# llrf_afe_fpga_conf.net
KiCad netlist of a schematic drawn in Altium Designer
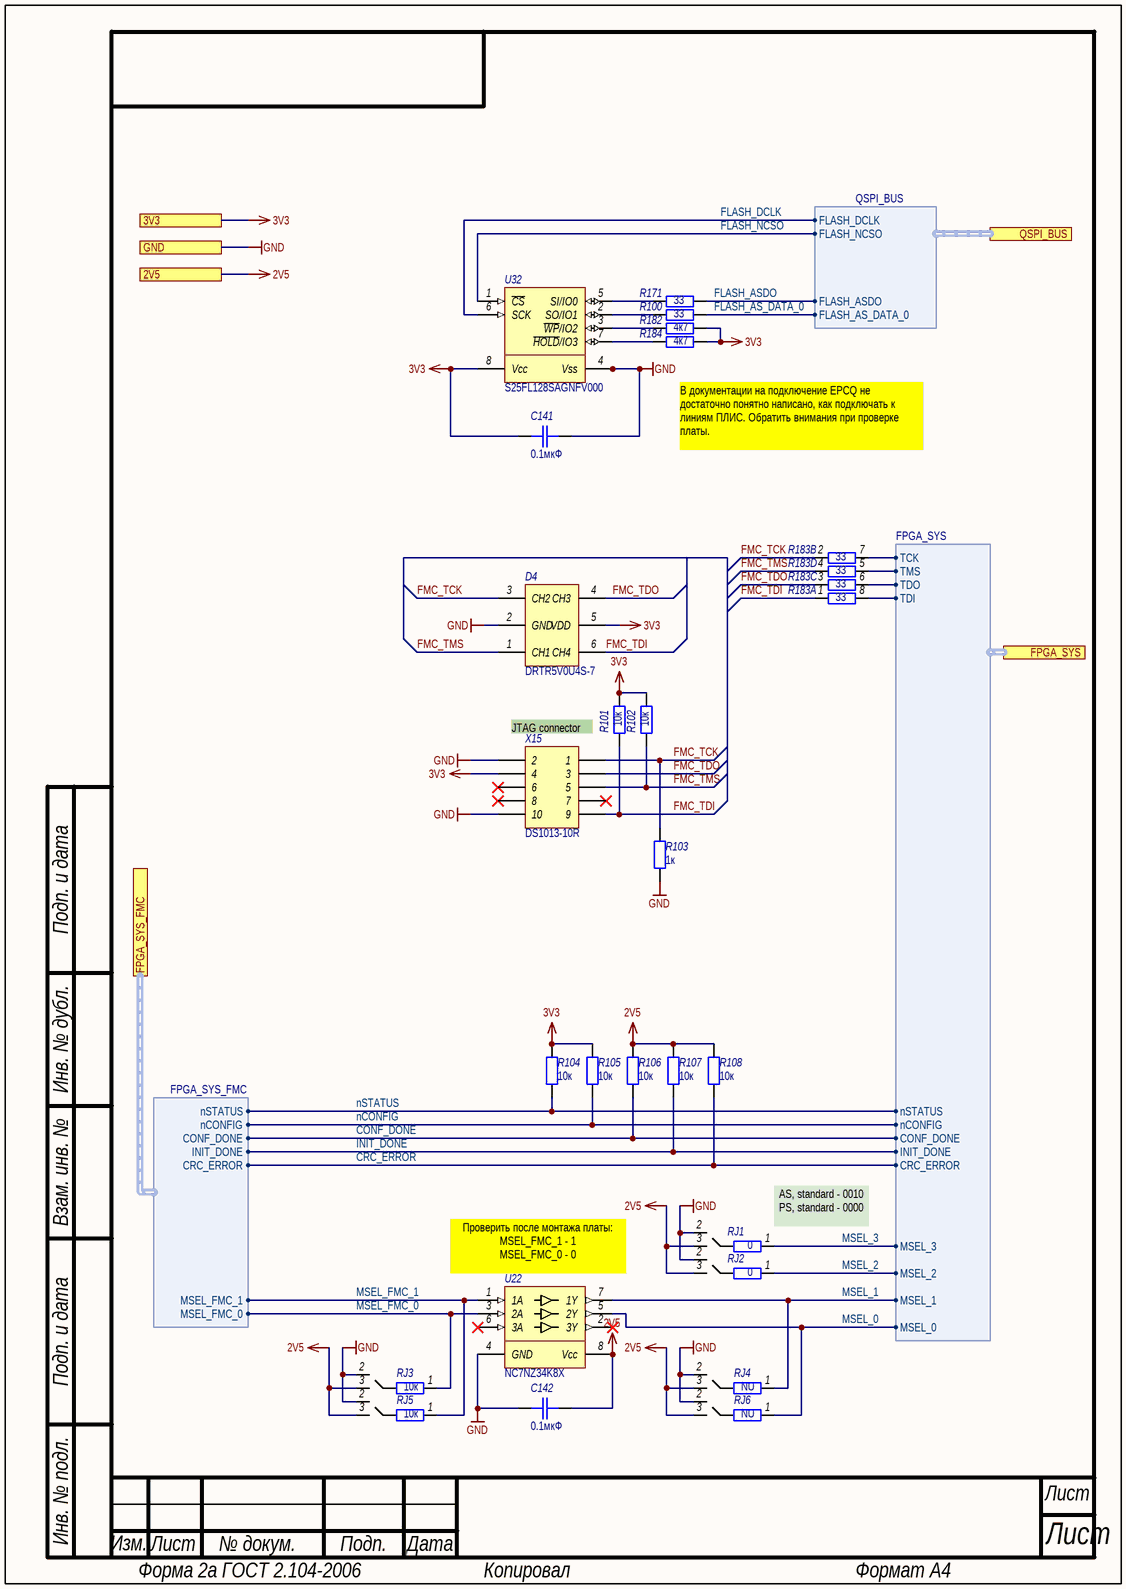
[diagram p0: llrf_afe_fpga_conf.SchDoc]

(export (version "E")
  (design (tool "Eeschema 10.0.6"))
  (components
    (comp (ref "C141")
      (value "0.1мкФ")
      (footprint "SMD_C0402")
      (description "Capacitor")
      (libsource (lib "Passive") (part "Capacitor"))
    )
    (comp (ref "C142")
      (value "0.1мкФ")
      (footprint "SMD_C0402")
      (description "Capacitor")
      (libsource (lib "Passive") (part "Capacitor"))
    )
    (comp (ref "D4")
      (value "DRTR5V0U4S")
      (footprint "SOT-363")
      (description "4 CHANNEL LOW CAPACITANCE TVS DIODE ARRAY")
      (fields (field (name "НАИМЕНОВАНИЕ") "DRTR5V0U4S-7"))
      (libsource (lib "Diod") (part "DRTR5V0U4S"))
    )
    (comp (ref "R100")
      (value "33")
      (footprint "SMD_0603")
      (description "PE1206DRM470R01L")
      (libsource (lib "Passive") (part "Resistor"))
    )
    (comp (ref "R101")
      (value "10к")
      (footprint "SMD_0603")
      (description "Resistor")
      (libsource (lib "") (part "Resistor_1"))
    )
    (comp (ref "R102")
      (value "10к")
      (footprint "SMD_0603")
      (description "Resistor")
      (libsource (lib "") (part "Resistor_1"))
    )
    (comp (ref "R103")
      (value "1к")
      (footprint "SMD_0603")
      (description "Resistor")
      (libsource (lib "") (part "Resistor_1"))
    )
    (comp (ref "R104")
      (value "10к")
      (footprint "SMD_0603")
      (description "Resistor")
      (libsource (lib "") (part "Resistor_1"))
    )
    (comp (ref "R105")
      (value "10к")
      (footprint "SMD_0603")
      (description "Resistor")
      (libsource (lib "") (part "Resistor_1"))
    )
    (comp (ref "R106")
      (value "10к")
      (footprint "SMD_0603")
      (description "Resistor")
      (libsource (lib "") (part "Resistor_1"))
    )
    (comp (ref "R107")
      (value "10к")
      (footprint "SMD_0603")
      (description "Resistor")
      (libsource (lib "") (part "Resistor_1"))
    )
    (comp (ref "R108")
      (value "10к")
      (footprint "SMD_0603")
      (description "Resistor")
      (libsource (lib "") (part "Resistor_1"))
    )
    (comp (ref "R171")
      (value "33")
      (footprint "SMD_0603")
      (description "PE1206DRM470R01L")
      (libsource (lib "Passive") (part "Resistor"))
    )
    (comp (ref "R182")
      (value "4к7")
      (footprint "SMD_0603")
      (description "Resistor")
      (libsource (lib "") (part "Resistor_2"))
    )
    (comp (ref "R183")
      (value "33")
      (footprint "TC124")
      (description "4 Chip Resistor Array")
      (libsource (lib "Passive") (part "Resistor-4"))
    )
    (comp (ref "R184")
      (value "4к7")
      (footprint "SMD_0603")
      (description "Resistor")
      (libsource (lib "") (part "Resistor_2"))
    )
    (comp (ref "RJ1")
      (value "0")
      (footprint "SMD_JMP_0603")
      (description "Resistor-Jumper")
      (libsource (lib "Passive") (part "Resistor_Jamper"))
    )
    (comp (ref "RJ2")
      (value "0")
      (footprint "SMD_JMP_0603")
      (description "Resistor-Jumper")
      (libsource (lib "Passive") (part "Resistor_Jamper"))
    )
    (comp (ref "RJ3")
      (value "10к")
      (footprint "SMD_JMP_0603")
      (description "Resistor-Jumper")
      (libsource (lib "Passive") (part "Resistor_Jamper"))
    )
    (comp (ref "RJ4")
      (value "NU")
      (footprint "SMD_JMP_0603")
      (description "Resistor-Jumper")
      (libsource (lib "Passive") (part "Resistor_Jamper"))
    )
    (comp (ref "RJ5")
      (value "10к")
      (footprint "SMD_JMP_0603")
      (description "Resistor-Jumper")
      (libsource (lib "Passive") (part "Resistor_Jamper"))
    )
    (comp (ref "RJ6")
      (value "NU")
      (footprint "SMD_JMP_0603")
      (description "Resistor-Jumper")
      (libsource (lib "Passive") (part "Resistor_Jamper"))
    )
    (comp (ref "U22")
      (value "NC7NZ34")
      (footprint "US-8")
      (description "TinyLogic UHS Triple Buffer")
      (fields (field (name "НАИМЕНОВАНИЕ") "NC7NZ34K8X"))
      (libsource (lib "Logic") (part "NC7NZ34"))
    )
    (comp (ref "U32")
      (value "S25FL128SAGN")
      (footprint "WSON-8_6x8")
      (description "Programmable NOR flash memory")
      (fields (field (name "НАИМЕНОВАНИЕ") "S25FL128SAGNFV000"))
      (libsource (lib "Memory") (part "S25FL128SAGN"))
    )
    (comp (ref "X15")
      (value "DS1013-10R")
      (footprint "DS1013-10R")
      (description "Header, 10-Pin, Dual row")
      (fields (field (name "НАИМЕНОВАНИЕ") "DS1013-10R"))
      (libsource (lib "Connector") (part "Header 2X10"))
    )
  )
  (nets
    (net (code "4") (name "/CONF_DONE") (class "Default")
      (node (ref "R106") (pin "1") (pinfunction "1_1") (pintype "passive"))
    )
    (net (code "5") (name "/CRC_ERROR") (class "Default")
      (node (ref "R108") (pin "1") (pinfunction "1_1") (pintype "passive"))
    )
    (net (code "6") (name "/FLASH_ASDO") (class "Default")
      (node (ref "R171") (pin "2") (pinfunction "2_2") (pintype "passive"))
    )
    (net (code "7") (name "/FLASH_AS_DATA_0") (class "Default")
      (node (ref "R100") (pin "2") (pinfunction "2_2") (pintype "passive"))
    )
    (net (code "8") (name "/FLASH_DCLK") (class "Default")
      (node (ref "U32") (pin "6") (pinfunction "SCK_6") (pintype "input"))
    )
    (net (code "9") (name "/FLASH_NCSO") (class "Default")
      (node (ref "U32") (pin "1") (pinfunction "~{CS}_1") (pintype "input"))
    )
    (net (code "10") (name "/FMC_TCK") (class "Default")
      (node (ref "D4") (pin "3") (pinfunction "СH2_3") (pintype "passive"))
      (node (ref "R103") (pin "2") (pinfunction "2_2") (pintype "passive"))
      (node (ref "R183") (pin "2") (pinfunction "2_2") (pintype "passive"))
      (node (ref "X15") (pin "1") (pinfunction "1_1") (pintype "passive"))
    )
    (net (code "11") (name "/FMC_TDI") (class "Default")
      (node (ref "D4") (pin "6") (pinfunction "СH4_6") (pintype "passive"))
      (node (ref "R101") (pin "1") (pinfunction "1_1") (pintype "passive"))
      (node (ref "R183") (pin "1") (pinfunction "1_1") (pintype "passive"))
      (node (ref "X15") (pin "9") (pinfunction "9_9") (pintype "passive"))
    )
    (net (code "12") (name "/FMC_TDO") (class "Default")
      (node (ref "D4") (pin "4") (pinfunction "СH3_4") (pintype "passive"))
      (node (ref "R183") (pin "3") (pinfunction "3_3") (pintype "passive"))
      (node (ref "X15") (pin "3") (pinfunction "3_3") (pintype "passive"))
    )
    (net (code "13") (name "/FMC_TMS") (class "Default")
      (node (ref "D4") (pin "1") (pinfunction "СH1_1") (pintype "passive"))
      (node (ref "R102") (pin "1") (pinfunction "1_1") (pintype "passive"))
      (node (ref "R183") (pin "4") (pinfunction "4_4") (pintype "passive"))
      (node (ref "X15") (pin "5") (pinfunction "5_5") (pintype "passive"))
    )
    (net (code "14") (name "/INIT_DONE") (class "Default")
      (node (ref "R107") (pin "1") (pinfunction "1_1") (pintype "passive"))
    )
    (net (code "15") (name "/MSEL_0") (class "Default")
      (node (ref "RJ6") (pin "1") (pintype "passive"))
      (node (ref "U22") (pin "5") (pinfunction "2Y_5") (pintype "output"))
    )
    (net (code "16") (name "/MSEL_1") (class "Default")
      (node (ref "RJ4") (pin "1") (pintype "passive"))
      (node (ref "U22") (pin "7") (pinfunction "1Y_7") (pintype "output"))
    )
    (net (code "17") (name "/MSEL_2") (class "Default") (node (ref "RJ2") (pin "1") (pintype "passive")))
    (net (code "18") (name "/MSEL_3") (class "Default") (node (ref "RJ1") (pin "1") (pintype "passive")))
    (net (code "19") (name "/MSEL_FMC_0") (class "Default")
      (node (ref "RJ3") (pin "1") (pintype "passive"))
      (node (ref "U22") (pin "3") (pinfunction "2A_3") (pintype "input"))
    )
    (net (code "20") (name "/MSEL_FMC_1") (class "Default")
      (node (ref "RJ5") (pin "1") (pintype "passive"))
      (node (ref "U22") (pin "1") (pinfunction "1A_1") (pintype "input"))
    )
    (net (code "21") (name "/TCK") (class "Default")
      (node (ref "R183") (pin "7") (pinfunction "7_7") (pintype "passive"))
    )
    (net (code "22") (name "/TDI") (class "Default")
      (node (ref "R183") (pin "8") (pinfunction "8_8") (pintype "passive"))
    )
    (net (code "23") (name "/TDO") (class "Default")
      (node (ref "R183") (pin "6") (pinfunction "6_6") (pintype "passive"))
    )
    (net (code "24") (name "/TMS") (class "Default")
      (node (ref "R183") (pin "5") (pinfunction "5_5") (pintype "passive"))
    )
    (net (code "25") (name "/nCONFIG") (class "Default")
      (node (ref "R105") (pin "1") (pinfunction "1_1") (pintype "passive"))
    )
    (net (code "26") (name "/nSTATUS") (class "Default")
      (node (ref "R104") (pin "1") (pinfunction "1_1") (pintype "passive"))
    )
    (net (code "30") (name "2V5") (class "Default")
      (node (ref "C142") (pin "2") (pinfunction "2_2") (pintype "passive"))
      (node (ref "R106") (pin "2") (pinfunction "2_2") (pintype "passive"))
      (node (ref "R107") (pin "2") (pinfunction "2_2") (pintype "passive"))
      (node (ref "R108") (pin "2") (pinfunction "2_2") (pintype "passive"))
      (node (ref "RJ1") (pin "3") (pintype "passive"))
      (node (ref "RJ2") (pin "3") (pintype "passive"))
      (node (ref "RJ3") (pin "3") (pintype "passive"))
      (node (ref "RJ4") (pin "3") (pintype "passive"))
      (node (ref "RJ5") (pin "3") (pintype "passive"))
      (node (ref "RJ6") (pin "3") (pintype "passive"))
      (node (ref "U22") (pin "8") (pinfunction "Vcc_8") (pintype "power_in"))
    )
    (net (code "31") (name "3V3") (class "Default")
      (node (ref "C141") (pin "2") (pinfunction "2_2") (pintype "passive"))
      (node (ref "D4") (pin "5") (pinfunction "VDD_5") (pintype "power_in"))
      (node (ref "R101") (pin "2") (pinfunction "2_2") (pintype "passive"))
      (node (ref "R102") (pin "2") (pinfunction "2_2") (pintype "passive"))
      (node (ref "R104") (pin "2") (pinfunction "2_2") (pintype "passive"))
      (node (ref "R105") (pin "2") (pinfunction "2_2") (pintype "passive"))
      (node (ref "R182") (pin "1") (pinfunction "1_1") (pintype "passive"))
      (node (ref "R184") (pin "1") (pinfunction "1_1") (pintype "passive"))
      (node (ref "U32") (pin "8") (pinfunction "Vcc_8") (pintype "power_in"))
      (node (ref "X15") (pin "4") (pinfunction "4_4") (pintype "passive"))
    )
    (net (code "32") (name "GND") (class "Default")
      (node (ref "C141") (pin "1") (pinfunction "1_1") (pintype "passive"))
      (node (ref "C142") (pin "1") (pinfunction "1_1") (pintype "passive"))
      (node (ref "D4") (pin "2") (pinfunction "GND_2") (pintype "power_in"))
      (node (ref "R103") (pin "1") (pinfunction "1_1") (pintype "passive"))
      (node (ref "RJ1") (pin "2") (pintype "passive"))
      (node (ref "RJ2") (pin "2") (pintype "passive"))
      (node (ref "RJ3") (pin "2") (pintype "passive"))
      (node (ref "RJ4") (pin "2") (pintype "passive"))
      (node (ref "RJ5") (pin "2") (pintype "passive"))
      (node (ref "RJ6") (pin "2") (pintype "passive"))
      (node (ref "U22") (pin "4") (pinfunction "GND_4") (pintype "power_in"))
      (node (ref "U32") (pin "4") (pinfunction "Vss_4") (pintype "power_in"))
      (node (ref "U32") (pin "9") (pinfunction "TP_9") (pintype "power_in"))
      (node (ref "X15") (pin "10") (pinfunction "10_10") (pintype "passive"))
      (node (ref "X15") (pin "2") (pinfunction "2_2") (pintype "passive"))
    )
    (net (code "33") (name "Net-(U32-SI{slash}IO0)") (class "Default")
      (node (ref "R171") (pin "1") (pinfunction "1_1") (pintype "passive"))
      (node (ref "U32") (pin "5") (pinfunction "SI/IO0_5") (pintype "bidirectional"))
    )
    (net (code "34") (name "Net-(U32-SO{slash}IO1)") (class "Default")
      (node (ref "R100") (pin "1") (pinfunction "1_1") (pintype "passive"))
      (node (ref "U32") (pin "2") (pinfunction "SO/IO1_2") (pintype "bidirectional"))
    )
    (net (code "35") (name "Net-(U32-~{HOLD}{slash}IO3)") (class "Default")
      (node (ref "R184") (pin "2") (pinfunction "2_2") (pintype "passive"))
      (node (ref "U32") (pin "7") (pinfunction "~{HOLD}/IO3_7") (pintype "bidirectional"))
    )
    (net (code "36") (name "Net-(U32-~{WP}{slash}IO2)") (class "Default")
      (node (ref "R182") (pin "2") (pinfunction "2_2") (pintype "passive"))
      (node (ref "U32") (pin "3") (pinfunction "~{WP}/IO2_3") (pintype "bidirectional"))
    )
    (net (code "37") (name "unconnected-(U22-3A-Pad6)") (class "Default")
      (node (ref "U22") (pin "6") (pinfunction "3A_6") (pintype "input+no_connect"))
    )
    (net (code "38") (name "unconnected-(U22-3Y-Pad2)") (class "Default")
      (node (ref "U22") (pin "2") (pinfunction "3Y_2") (pintype "output+no_connect"))
    )
    (net (code "39") (name "unconnected-(X15-Pad6)") (class "Default")
      (node (ref "X15") (pin "6") (pinfunction "6_6") (pintype "passive+no_connect"))
    )
    (net (code "40") (name "unconnected-(X15-Pad7)") (class "Default")
      (node (ref "X15") (pin "7") (pinfunction "7_7") (pintype "passive+no_connect"))
    )
    (net (code "41") (name "unconnected-(X15-Pad8)") (class "Default")
      (node (ref "X15") (pin "8") (pinfunction "8_8") (pintype "passive+no_connect"))
    )
  )
)
